# ctrl_bottom.net
KiCad netlist of a schematic drawn in EAGLE
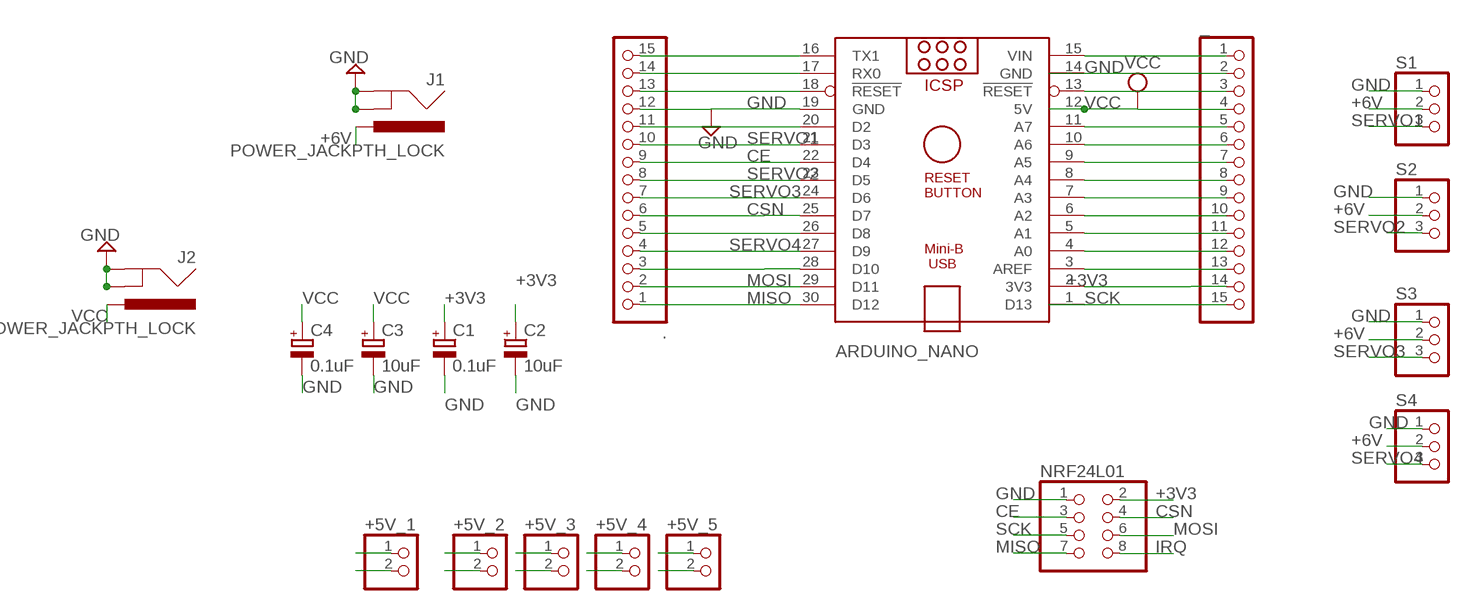
[diagram p0: schematic, sheet 1]

(export (version "E")
  (design (tool "Eeschema 10.0.6"))
  (components
    (comp (ref "+5V_1")
      (value "PINHD-1X2")
      (footprint "eagle-import:1X02")
      (libsource (lib "eagle-import") (part "PINHD-1X2"))
    )
    (comp (ref "+5V_2")
      (value "PINHD-1X2")
      (footprint "eagle-import:1X02")
      (libsource (lib "eagle-import") (part "PINHD-1X2"))
    )
    (comp (ref "+5V_3")
      (value "PINHD-1X2")
      (footprint "eagle-import:1X02")
      (libsource (lib "eagle-import") (part "PINHD-1X2"))
    )
    (comp (ref "+5V_4")
      (value "PINHD-1X2")
      (footprint "eagle-import:1X02")
      (libsource (lib "eagle-import") (part "PINHD-1X2"))
    )
    (comp (ref "+5V_5")
      (value "PINHD-1X2")
      (footprint "eagle-import:1X02")
      (libsource (lib "eagle-import") (part "PINHD-1X2"))
    )
    (comp (ref ".")
      (value "PINHD-1X15")
      (footprint "eagle-import:1X15")
      (libsource (lib "eagle-import") (part "PINHD-1X15"))
    )
    (comp (ref "ARDUINO_NANO")
      (value "ARDUINO_NANO")
      (footprint "eagle-import:ARDUINO_NANO")
      (libsource (lib "eagle-import") (part "ARDUINO_NANO"))
    )
    (comp (ref "C1")
      (value "0.1uF")
      (footprint "eagle-import:E1,8-4")
      (libsource (lib "eagle-import") (part "CPOL-EUE1.8-4"))
    )
    (comp (ref "C2")
      (value "10uF")
      (footprint "eagle-import:E1,8-4")
      (libsource (lib "eagle-import") (part "CPOL-EUE1.8-4"))
    )
    (comp (ref "C3")
      (value "10uF")
      (footprint "eagle-import:E1,8-4")
      (libsource (lib "eagle-import") (part "CPOL-EUE1.8-4"))
    )
    (comp (ref "C4")
      (value "0.1uF")
      (footprint "eagle-import:E1,8-4")
      (libsource (lib "eagle-import") (part "CPOL-EUE1.8-4"))
    )
    (comp (ref "J1")
      (value "POWER_JACKPTH_LOCK")
      (footprint "eagle-import:POWER_JACK_PTH_LOCK")
      (libsource (lib "eagle-import") (part "POWER_JACKPTH_LOCK"))
    )
    (comp (ref "J2")
      (value "POWER_JACKPTH_LOCK")
      (footprint "eagle-import:POWER_JACK_PTH_LOCK")
      (libsource (lib "eagle-import") (part "POWER_JACKPTH_LOCK"))
    )
    (comp (ref "NRF24L01")
      (value "PINHD-2X4")
      (footprint "eagle-import:2X04")
      (libsource (lib "eagle-import") (part "PINHD-2X4"))
    )
    (comp (ref "S1")
      (value "PINHD-1X3")
      (footprint "eagle-import:1X03")
      (libsource (lib "eagle-import") (part "PINHD-1X3"))
    )
    (comp (ref "S2")
      (value "PINHD-1X3")
      (footprint "eagle-import:1X03")
      (libsource (lib "eagle-import") (part "PINHD-1X3"))
    )
    (comp (ref "S3")
      (value "PINHD-1X3")
      (footprint "eagle-import:1X03")
      (libsource (lib "eagle-import") (part "PINHD-1X3"))
    )
    (comp (ref "S4")
      (value "PINHD-1X3")
      (footprint "eagle-import:1X03")
      (libsource (lib "eagle-import") (part "PINHD-1X3"))
    )
    (comp (ref "_")
      (value "PINHD-1X15")
      (footprint "eagle-import:1X15")
      (libsource (lib "eagle-import") (part "PINHD-1X15"))
    )
  )
  (nets
    (net (code "1") (name "/+3V3") (class "Default")
      (node (ref "ARDUINO_NANO") (pin "2") (pinfunction "3V3_2") (pintype "output"))
      (node (ref "C1") (pin "+") (pinfunction "+_+") (pintype "passive"))
      (node (ref "C2") (pin "+") (pinfunction "+_+") (pintype "passive"))
      (node (ref "NRF24L01") (pin "2") (pinfunction "2_2") (pintype "passive"))
      (node (ref "_") (pin "14") (pinfunction "14_14") (pintype "passive"))
    )
    (net (code "2") (name "/+6V") (class "Default")
      (node (ref "J1") (pin "PWR") (pinfunction "PWR_PWR") (pintype "bidirectional"))
      (node (ref "S1") (pin "2") (pinfunction "2_2") (pintype "passive"))
      (node (ref "S2") (pin "2") (pinfunction "2_2") (pintype "passive"))
      (node (ref "S3") (pin "2") (pinfunction "2_2") (pintype "passive"))
      (node (ref "S4") (pin "2") (pinfunction "2_2") (pintype "passive"))
    )
    (net (code "3") (name "/CE") (class "Default")
      (node (ref ".") (pin "9") (pinfunction "9_9") (pintype "passive"))
      (node (ref "ARDUINO_NANO") (pin "22") (pinfunction "D4_22") (pintype "bidirectional"))
      (node (ref "NRF24L01") (pin "3") (pinfunction "3_3") (pintype "passive"))
    )
    (net (code "4") (name "/CSN") (class "Default")
      (node (ref ".") (pin "6") (pinfunction "6_6") (pintype "passive"))
      (node (ref "ARDUINO_NANO") (pin "25") (pinfunction "D7_25") (pintype "bidirectional"))
      (node (ref "NRF24L01") (pin "4") (pinfunction "4_4") (pintype "passive"))
    )
    (net (code "5") (name "/IRQ") (class "Default")
      (node (ref "NRF24L01") (pin "8") (pinfunction "8_8") (pintype "passive"))
    )
    (net (code "6") (name "/MISO") (class "Default")
      (node (ref ".") (pin "1") (pinfunction "1_1") (pintype "passive"))
      (node (ref "ARDUINO_NANO") (pin "30") (pinfunction "D12_30") (pintype "bidirectional"))
      (node (ref "NRF24L01") (pin "7") (pinfunction "7_7") (pintype "passive"))
    )
    (net (code "7") (name "/MOSI") (class "Default")
      (node (ref ".") (pin "2") (pinfunction "2_2") (pintype "passive"))
      (node (ref "ARDUINO_NANO") (pin "29") (pinfunction "D11_29") (pintype "bidirectional"))
      (node (ref "NRF24L01") (pin "6") (pinfunction "6_6") (pintype "passive"))
    )
    (net (code "8") (name "/N$2") (class "Default")
      (node (ref ".") (pin "3") (pinfunction "3_3") (pintype "passive"))
      (node (ref "ARDUINO_NANO") (pin "28") (pinfunction "D10_28") (pintype "bidirectional"))
    )
    (net (code "9") (name "/SCK") (class "Default")
      (node (ref "ARDUINO_NANO") (pin "1") (pinfunction "D13_1") (pintype "bidirectional"))
      (node (ref "NRF24L01") (pin "5") (pinfunction "5_5") (pintype "passive"))
      (node (ref "_") (pin "15") (pinfunction "15_15") (pintype "passive"))
    )
    (net (code "10") (name "/SERVO1") (class "Default")
      (node (ref ".") (pin "10") (pinfunction "10_10") (pintype "passive"))
      (node (ref "ARDUINO_NANO") (pin "21") (pinfunction "D3_21") (pintype "bidirectional"))
      (node (ref "S1") (pin "3") (pinfunction "3_3") (pintype "passive"))
    )
    (net (code "11") (name "/SERVO2") (class "Default")
      (node (ref ".") (pin "8") (pinfunction "8_8") (pintype "passive"))
      (node (ref "ARDUINO_NANO") (pin "23") (pinfunction "D5_23") (pintype "bidirectional"))
      (node (ref "S2") (pin "3") (pinfunction "3_3") (pintype "passive"))
    )
    (net (code "12") (name "/SERVO3") (class "Default")
      (node (ref ".") (pin "7") (pinfunction "7_7") (pintype "passive"))
      (node (ref "ARDUINO_NANO") (pin "24") (pinfunction "D6_24") (pintype "bidirectional"))
      (node (ref "S3") (pin "3") (pinfunction "3_3") (pintype "passive"))
    )
    (net (code "13") (name "/SERVO4") (class "Default")
      (node (ref ".") (pin "4") (pinfunction "4_4") (pintype "passive"))
      (node (ref "ARDUINO_NANO") (pin "27") (pinfunction "D9_27") (pintype "bidirectional"))
      (node (ref "S4") (pin "3") (pinfunction "3_3") (pintype "passive"))
    )
    (net (code "14") (name "GND") (class "Default")
      (node (ref "+5V_1") (pin "2") (pinfunction "2_2") (pintype "passive"))
      (node (ref "+5V_2") (pin "2") (pinfunction "2_2") (pintype "passive"))
      (node (ref "+5V_3") (pin "2") (pinfunction "2_2") (pintype "passive"))
      (node (ref "+5V_4") (pin "2") (pinfunction "2_2") (pintype "passive"))
      (node (ref "+5V_5") (pin "2") (pinfunction "2_2") (pintype "passive"))
      (node (ref ".") (pin "12") (pinfunction "12_12") (pintype "passive"))
      (node (ref "ARDUINO_NANO") (pin "14") (pinfunction "GND_14") (pintype "power_in"))
      (node (ref "ARDUINO_NANO") (pin "19") (pinfunction "GND_19") (pintype "power_in"))
      (node (ref "C1") (pin "-") (pinfunction "-_-") (pintype "passive"))
      (node (ref "C2") (pin "-") (pinfunction "-_-") (pintype "passive"))
      (node (ref "C3") (pin "-") (pinfunction "-_-") (pintype "passive"))
      (node (ref "C4") (pin "-") (pinfunction "-_-") (pintype "passive"))
      (node (ref "J1") (pin "GND") (pinfunction "GND_GND") (pintype "bidirectional"))
      (node (ref "J1") (pin "GNDBREAK") (pinfunction "GNDBREAK_GNDBREAK") (pintype "bidirectional"))
      (node (ref "J2") (pin "GND") (pinfunction "GND_GND") (pintype "bidirectional"))
      (node (ref "J2") (pin "GNDBREAK") (pinfunction "GNDBREAK_GNDBREAK") (pintype "bidirectional"))
      (node (ref "NRF24L01") (pin "1") (pinfunction "1_1") (pintype "passive"))
      (node (ref "S1") (pin "1") (pinfunction "1_1") (pintype "passive"))
      (node (ref "S2") (pin "1") (pinfunction "1_1") (pintype "passive"))
      (node (ref "S3") (pin "1") (pinfunction "1_1") (pintype "passive"))
      (node (ref "S4") (pin "1") (pinfunction "1_1") (pintype "passive"))
      (node (ref "_") (pin "2") (pinfunction "2_2") (pintype "passive"))
    )
    (net (code "15") (name "Net-(.-Pad13)") (class "Default")
      (node (ref ".") (pin "13") (pinfunction "13_13") (pintype "passive"))
      (node (ref "ARDUINO_NANO") (pin "18") (pinfunction "~{RESET}_18") (pintype "input"))
    )
    (net (code "16") (name "Net-(ARDUINO_NANO-A0)") (class "Default")
      (node (ref "ARDUINO_NANO") (pin "4") (pinfunction "A0_4") (pintype "bidirectional"))
      (node (ref "_") (pin "12") (pinfunction "12_12") (pintype "passive"))
    )
    (net (code "17") (name "Net-(ARDUINO_NANO-A1)") (class "Default")
      (node (ref "ARDUINO_NANO") (pin "5") (pinfunction "A1_5") (pintype "bidirectional"))
      (node (ref "_") (pin "11") (pinfunction "11_11") (pintype "passive"))
    )
    (net (code "18") (name "Net-(ARDUINO_NANO-A2)") (class "Default")
      (node (ref "ARDUINO_NANO") (pin "6") (pinfunction "A2_6") (pintype "bidirectional"))
      (node (ref "_") (pin "10") (pinfunction "10_10") (pintype "passive"))
    )
    (net (code "19") (name "Net-(ARDUINO_NANO-A3)") (class "Default")
      (node (ref "ARDUINO_NANO") (pin "7") (pinfunction "A3_7") (pintype "bidirectional"))
      (node (ref "_") (pin "9") (pinfunction "9_9") (pintype "passive"))
    )
    (net (code "20") (name "Net-(ARDUINO_NANO-A4)") (class "Default")
      (node (ref "ARDUINO_NANO") (pin "8") (pinfunction "A4_8") (pintype "bidirectional"))
      (node (ref "_") (pin "8") (pinfunction "8_8") (pintype "passive"))
    )
    (net (code "21") (name "Net-(ARDUINO_NANO-A5)") (class "Default")
      (node (ref "ARDUINO_NANO") (pin "9") (pinfunction "A5_9") (pintype "bidirectional"))
      (node (ref "_") (pin "7") (pinfunction "7_7") (pintype "passive"))
    )
    (net (code "22") (name "Net-(ARDUINO_NANO-A6)") (class "Default")
      (node (ref "ARDUINO_NANO") (pin "10") (pinfunction "A6_10") (pintype "bidirectional"))
      (node (ref "_") (pin "6") (pinfunction "6_6") (pintype "passive"))
    )
    (net (code "23") (name "Net-(ARDUINO_NANO-A7)") (class "Default")
      (node (ref "ARDUINO_NANO") (pin "11") (pinfunction "A7_11") (pintype "bidirectional"))
      (node (ref "_") (pin "5") (pinfunction "5_5") (pintype "passive"))
    )
    (net (code "24") (name "Net-(ARDUINO_NANO-AREF)") (class "Default")
      (node (ref "ARDUINO_NANO") (pin "3") (pinfunction "AREF_3") (pintype "input"))
      (node (ref "_") (pin "13") (pinfunction "13_13") (pintype "passive"))
    )
    (net (code "25") (name "Net-(ARDUINO_NANO-D2)") (class "Default")
      (node (ref ".") (pin "11") (pinfunction "11_11") (pintype "passive"))
      (node (ref "ARDUINO_NANO") (pin "20") (pinfunction "D2_20") (pintype "bidirectional"))
    )
    (net (code "26") (name "Net-(ARDUINO_NANO-D8)") (class "Default")
      (node (ref ".") (pin "5") (pinfunction "5_5") (pintype "passive"))
      (node (ref "ARDUINO_NANO") (pin "26") (pinfunction "D8_26") (pintype "bidirectional"))
    )
    (net (code "27") (name "Net-(ARDUINO_NANO-RX0)") (class "Default")
      (node (ref ".") (pin "14") (pinfunction "14_14") (pintype "passive"))
      (node (ref "ARDUINO_NANO") (pin "17") (pinfunction "RX0_17") (pintype "bidirectional"))
    )
    (net (code "28") (name "Net-(ARDUINO_NANO-TX1)") (class "Default")
      (node (ref ".") (pin "15") (pinfunction "15_15") (pintype "passive"))
      (node (ref "ARDUINO_NANO") (pin "16") (pinfunction "TX1_16") (pintype "bidirectional"))
    )
    (net (code "29") (name "Net-(ARDUINO_NANO-VIN)") (class "Default")
      (node (ref "ARDUINO_NANO") (pin "15") (pinfunction "VIN_15") (pintype "power_in"))
      (node (ref "_") (pin "1") (pinfunction "1_1") (pintype "passive"))
    )
    (net (code "30") (name "Net-(ARDUINO_NANO-~{RESET}-Pad13)") (class "Default")
      (node (ref "ARDUINO_NANO") (pin "13") (pinfunction "~{RESET}_13") (pintype "input"))
      (node (ref "_") (pin "3") (pinfunction "3_3") (pintype "passive"))
    )
    (net (code "31") (name "VCC") (class "Default")
      (node (ref "+5V_1") (pin "1") (pinfunction "1_1") (pintype "passive"))
      (node (ref "+5V_2") (pin "1") (pinfunction "1_1") (pintype "passive"))
      (node (ref "+5V_3") (pin "1") (pinfunction "1_1") (pintype "passive"))
      (node (ref "+5V_4") (pin "1") (pinfunction "1_1") (pintype "passive"))
      (node (ref "+5V_5") (pin "1") (pinfunction "1_1") (pintype "passive"))
      (node (ref "ARDUINO_NANO") (pin "12") (pinfunction "5V_12") (pintype "power_in"))
      (node (ref "C3") (pin "+") (pinfunction "+_+") (pintype "passive"))
      (node (ref "C4") (pin "+") (pinfunction "+_+") (pintype "passive"))
      (node (ref "J2") (pin "PWR") (pinfunction "PWR_PWR") (pintype "bidirectional"))
      (node (ref "_") (pin "4") (pinfunction "4_4") (pintype "passive"))
    )
  )
)
